# home-connection.net
KiCad netlist of a schematic drawn in EasyEDA Pro
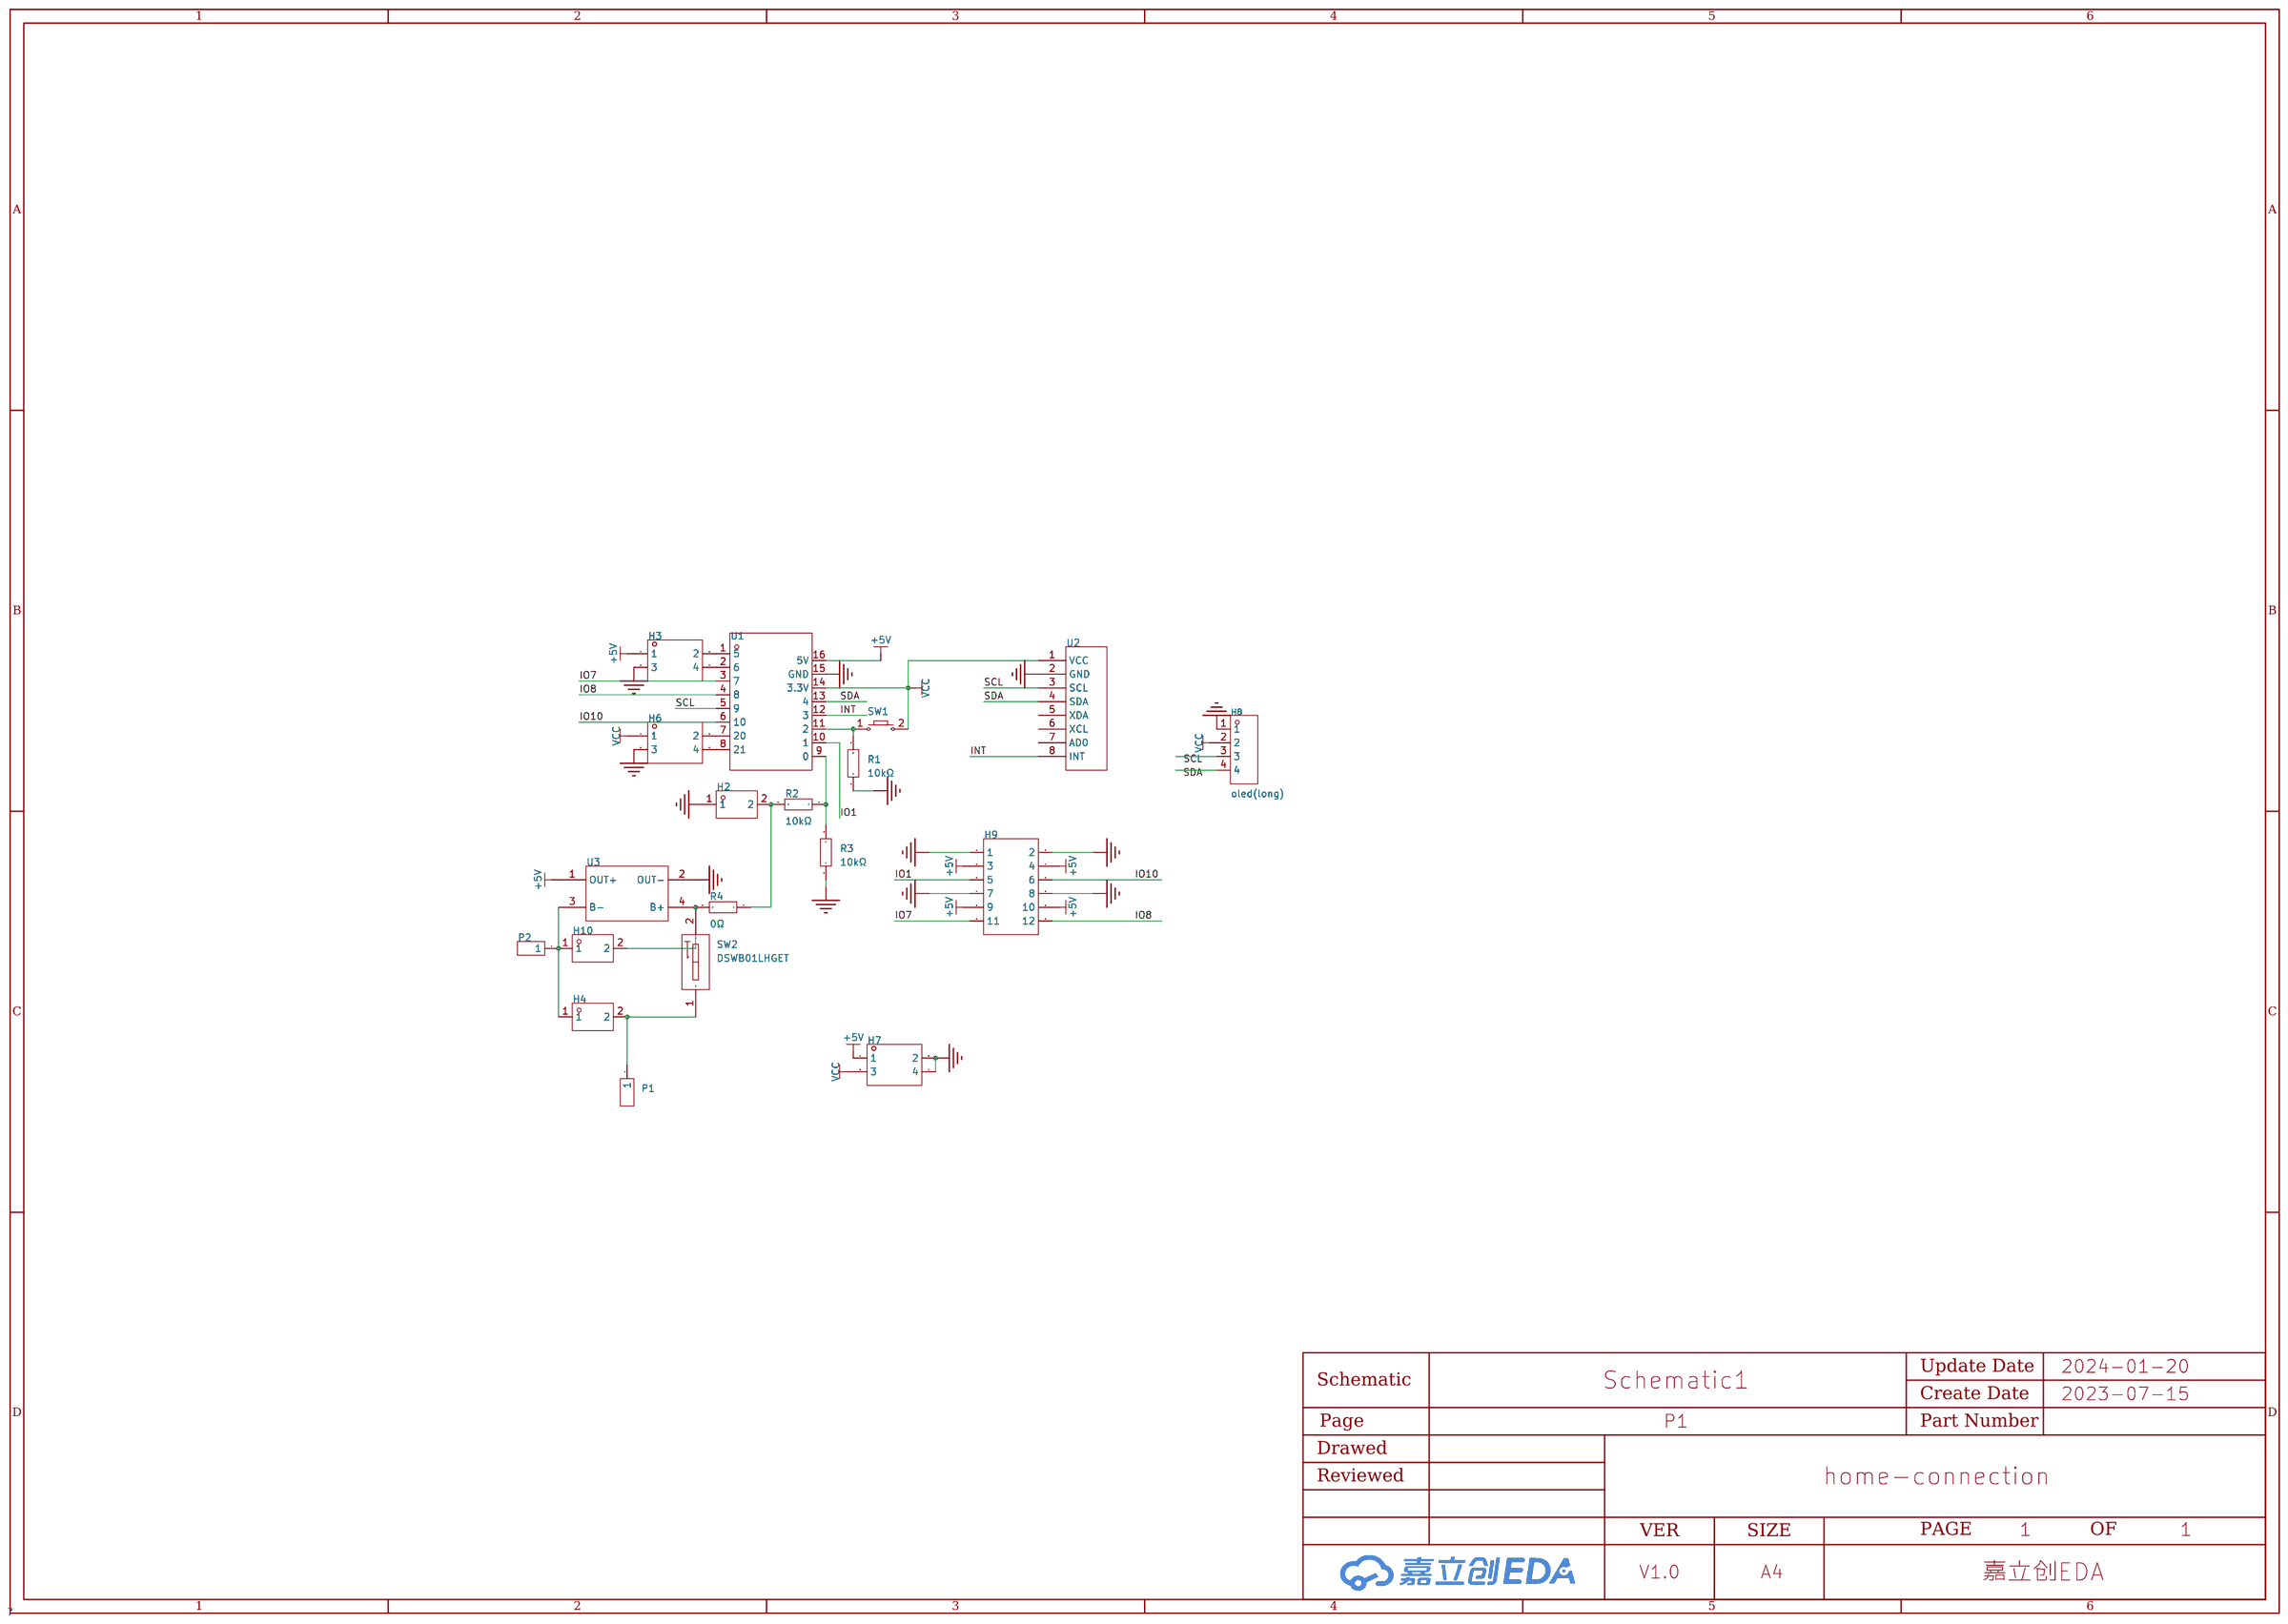
[diagram p0: schematic sheet]

(export (version "E")
  (design (tool "Eeschema 10.0.6"))
  (components
    (comp (ref "H2")
      (value "~")
      (footprint "easyedapro:HDR-TH_2P-P2.54-V-M-2")
      (libsource (lib "easyedapro") (part "HDR-M-2.54_2x1"))
    )
    (comp (ref "H3")
      (value "~")
      (footprint "easyedapro:HDR-TH_4P-P2.54-V-F-R2-C2-S2.54")
      (libsource (lib "easyedapro") (part "HDR-F-2.54_2x2"))
    )
    (comp (ref "H4")
      (value "~")
      (footprint "easyedapro:HDR-TH_2P-P2.54-V-M-2")
      (libsource (lib "easyedapro") (part "HDR-M-2.54_2x1"))
    )
    (comp (ref "H6")
      (value "~")
      (footprint "easyedapro:HDR-TH_4P-P2.54-V-F-R2-C2-S2.54")
      (libsource (lib "easyedapro") (part "HDR-F-2.54_2x2"))
    )
    (comp (ref "H7")
      (value "~")
      (footprint "easyedapro:HDR-TH_4P-P2.54-V-F-R2-C2-S2.54")
      (libsource (lib "easyedapro") (part "HDR-F-2.54_2x2"))
    )
    (comp (ref "H8")
      (value "oled(long)")
      (footprint "easyedapro:HDR-TH_4P-P2.54-V-M")
      (fields (field (name "Manufacturer") "XFCN(兴飞)"))
      (libsource (lib "easyedapro") (part "PZ254V-11-04P_C2691448"))
    )
    (comp (ref "H9")
      (value "~")
      (footprint "easyedapro:HDR-TH_12P-P2.54-V-M-R2-C6-S2.54")
      (libsource (lib "easyedapro") (part "HDR-F-2.54_2x6"))
    )
    (comp (ref "H10")
      (value "~")
      (footprint "easyedapro:HDR-TH_2P-P2.54-V-M-2")
      (libsource (lib "easyedapro") (part "HDR-M-2.54_2x1"))
    )
    (comp (ref "P1")
      (value "~")
      (footprint "easyedapro:HDR-TH_1P-P2.54-V-M")
      (description "间距:-;总PIN位数:1;排数:1;插针结构:-;行距:-;安装类型:直插;圆针/方针:-;额定电流:-;额定电压:-;配合针长度:-;塑高:-;触头材质:-;触头镀层:-;颜色:黑色;")
      (fields (field (name "Manufacturer Part") "2.54-1*1P针") (field (name "Manufacturer") "BOOMELE(博穆精密)"))
      (libsource (lib "easyedapro") (part "Header-Male-2.54_1x1"))
    )
    (comp (ref "P2")
      (value "~")
      (footprint "easyedapro:HDR-TH_1P-P2.54-V-M")
      (description "间距:-;总PIN位数:1;排数:1;插针结构:-;行距:-;安装类型:直插;圆针/方针:-;额定电流:-;额定电压:-;配合针长度:-;塑高:-;触头材质:-;触头镀层:-;颜色:黑色;")
      (fields (field (name "Manufacturer Part") "2.54-1*1P针") (field (name "Manufacturer") "BOOMELE(博穆精密)"))
      (libsource (lib "easyedapro") (part "Header-Male-2.54_1x1"))
    )
    (comp (ref "R1")
      (value "10kΩ")
      (footprint "easyedapro:R0603")
      (description "电阻类型:厚膜电阻;阻值:10kΩ;精度:±1%;功率:100mW;")
      (fields
        (field (name "Manufacturer Part") "0603WAF1002T5E")
        (field (name "Manufacturer") "UNI-ROYAL(厚声)")
      )
      (libsource (lib "easyedapro") (part "0603WAF1002T5E"))
    )
    (comp (ref "R2")
      (value "10kΩ")
      (footprint "easyedapro:R0603")
      (description "电阻类型:厚膜电阻;阻值:10kΩ;精度:±1%;功率:100mW;")
      (fields
        (field (name "Manufacturer Part") "0603WAF1002T5E")
        (field (name "Manufacturer") "UNI-ROYAL(厚声)")
      )
      (libsource (lib "easyedapro") (part "0603WAF1002T5E"))
    )
    (comp (ref "R3")
      (value "10kΩ")
      (footprint "easyedapro:R0603")
      (description "电阻类型:厚膜电阻;阻值:10kΩ;精度:±1%;功率:100mW;")
      (fields
        (field (name "Manufacturer Part") "0603WAF1002T5E")
        (field (name "Manufacturer") "UNI-ROYAL(厚声)")
      )
      (libsource (lib "easyedapro") (part "0603WAF1002T5E"))
    )
    (comp (ref "R4")
      (value "0Ω")
      (footprint "easyedapro:R0603")
      (description "电阻类型:厚膜电阻;阻值:10kΩ;精度:±1%;功率:100mW;")
      (fields
        (field (name "Manufacturer Part") "0603WAF1002T5E")
        (field (name "Manufacturer") "UNI-ROYAL(厚声)")
      )
      (libsource (lib "easyedapro") (part "0603WAF1002T5E"))
    )
    (comp (ref "SW1")
      (value "~")
      (footprint "easyedapro:Key_SMD_3x4x2")
      (libsource (lib "easyedapro") (part "轻触按键x2"))
    )
    (comp (ref "SW2")
      (value "DSWB01LHGET")
      (footprint "easyedapro:SW-TH_DSWB01LHGET")
      (description "类型:平拨,凸起式;电路结构:单刀单掷;开关位数:1;使用寿命:-;颜色:红色;")
      (fields (field (name "Manufacturer") "YE"))
      (libsource (lib "easyedapro") (part "DSWB01LHGET"))
    )
    (comp (ref "U1")
      (value "2.4GHz")
      (footprint "easyedapro:ESP32-C3-SUPERMINI")
      (description "核心处理器:ESP32-C3芯片;频率:2.4GHz;发射功率:20.5dBm;")
      (fields
        (field (name "Manufacturer Part") "ESP32-C3-WROOM-02U-N4")
        (field (name "Manufacturer") "ESPRESSIF(乐鑫)")
      )
      (libsource (lib "easyedapro") (part "ESP32-C3-SUPERMINI"))
    )
    (comp (ref "U2")
      (value "~")
      (footprint "easyedapro:GY-521")
      (description "MPU6050")
      (libsource (lib "easyedapro") (part "GY-521"))
    )
    (comp (ref "U3")
      (value "~")
      (footprint "easyedapro:BAT-CHARGE")
      (description "电池充电模块")
      (libsource (lib "easyedapro") (part "BAT-CHARGE"))
    )
  )
  (nets
    (net (code "1") (name "+5V") (class "Default")
      (node (ref "H3") (pin "1") (pinfunction "1_1") (pintype "input"))
      (node (ref "H7") (pin "1") (pinfunction "1_1") (pintype "input"))
      (node (ref "H9") (pin "10") (pinfunction "10_10") (pintype "input"))
      (node (ref "H9") (pin "3") (pinfunction "3_3") (pintype "input"))
      (node (ref "H9") (pin "4") (pinfunction "4_4") (pintype "input"))
      (node (ref "H9") (pin "9") (pinfunction "9_9") (pintype "input"))
      (node (ref "U1") (pin "16") (pinfunction "5V_16") (pintype "unspecified"))
      (node (ref "U3") (pin "1") (pinfunction "OUT+_1") (pintype "input"))
    )
    (net (code "2") (name "/INT") (class "Default")
      (node (ref "U1") (pin "12") (pinfunction "3_12") (pintype "bidirectional"))
      (node (ref "U2") (pin "8") (pinfunction "INT_8") (pintype "input"))
    )
    (net (code "3") (name "/IO1") (class "Default")
      (node (ref "H9") (pin "5") (pinfunction "5_5") (pintype "input"))
      (node (ref "U1") (pin "10") (pinfunction "1_10") (pintype "bidirectional"))
    )
    (net (code "4") (name "/IO7") (class "Default")
      (node (ref "H9") (pin "11") (pinfunction "11_11") (pintype "input"))
      (node (ref "U1") (pin "3") (pinfunction "7_3") (pintype "unspecified"))
    )
    (net (code "5") (name "/IO8") (class "Default")
      (node (ref "H9") (pin "12") (pinfunction "12_12") (pintype "input"))
      (node (ref "U1") (pin "4") (pinfunction "8_4") (pintype "unspecified"))
    )
    (net (code "6") (name "/IO10") (class "Default")
      (node (ref "H9") (pin "6") (pinfunction "6_6") (pintype "input"))
      (node (ref "U1") (pin "6") (pinfunction "10_6") (pintype "unspecified"))
    )
    (net (code "7") (name "/SCL") (class "Default")
      (node (ref "H8") (pin "3") (pinfunction "3_3") (pintype "input"))
      (node (ref "U1") (pin "5") (pinfunction "9_5") (pintype "unspecified"))
      (node (ref "U2") (pin "3") (pinfunction "SCL_3") (pintype "input"))
    )
    (net (code "8") (name "/SDA") (class "Default")
      (node (ref "H8") (pin "4") (pinfunction "4_4") (pintype "input"))
      (node (ref "U1") (pin "13") (pinfunction "4_13") (pintype "bidirectional"))
      (node (ref "U2") (pin "4") (pinfunction "SDA_4") (pintype "input"))
    )
    (net (code "9") (name "GND") (class "Default")
      (node (ref "H2") (pin "1") (pinfunction "1_1") (pintype "input"))
      (node (ref "H3") (pin "3") (pinfunction "3_3") (pintype "input"))
      (node (ref "H6") (pin "3") (pinfunction "3_3") (pintype "input"))
      (node (ref "H7") (pin "2") (pinfunction "2_2") (pintype "input"))
      (node (ref "H7") (pin "4") (pinfunction "4_4") (pintype "input"))
      (node (ref "H8") (pin "1") (pinfunction "1_1") (pintype "input"))
      (node (ref "H9") (pin "1") (pinfunction "1_1") (pintype "input"))
      (node (ref "H9") (pin "2") (pinfunction "2_2") (pintype "input"))
      (node (ref "H9") (pin "7") (pinfunction "7_7") (pintype "input"))
      (node (ref "H9") (pin "8") (pinfunction "8_8") (pintype "input"))
      (node (ref "R1") (pin "1") (pinfunction "1_1") (pintype "input"))
      (node (ref "R3") (pin "1") (pinfunction "1_1") (pintype "input"))
      (node (ref "U1") (pin "15") (pinfunction "GND_15") (pintype "unspecified"))
      (node (ref "U2") (pin "2") (pinfunction "GND_2") (pintype "input"))
      (node (ref "U3") (pin "2") (pinfunction "OUT-_2") (pintype "input"))
    )
    (net (code "10") (name "Net-(H2-Pad2)") (class "Default")
      (node (ref "H2") (pin "2") (pinfunction "2_2") (pintype "input"))
      (node (ref "R2") (pin "2") (pinfunction "2_2") (pintype "input"))
      (node (ref "R4") (pin "1") (pinfunction "1_1") (pintype "input"))
    )
    (net (code "11") (name "Net-(SW2-A1)") (class "Default")
      (node (ref "H4") (pin "2") (pinfunction "2_2") (pintype "input"))
      (node (ref "P1") (pin "1") (pinfunction "1_1") (pintype "input"))
      (node (ref "SW2") (pin "1") (pinfunction "A1_1") (pintype "input"))
    )
    (net (code "12") (name "Net-(U1-0)") (class "Default")
      (node (ref "R2") (pin "1") (pinfunction "1_1") (pintype "input"))
      (node (ref "R3") (pin "2") (pinfunction "2_2") (pintype "input"))
      (node (ref "U1") (pin "9") (pinfunction "0_9") (pintype "unspecified"))
    )
    (net (code "13") (name "Net-(U1-2)") (class "Default")
      (node (ref "R1") (pin "2") (pinfunction "2_2") (pintype "input"))
      (node (ref "SW1") (pin "1") (pinfunction "1_1") (pintype "input"))
      (node (ref "U1") (pin "11") (pinfunction "2_11") (pintype "unspecified"))
    )
    (net (code "14") (name "Net-(U1-5)") (class "Default")
      (node (ref "H3") (pin "2") (pinfunction "2_2") (pintype "input"))
      (node (ref "U1") (pin "1") (pinfunction "5_1") (pintype "unspecified"))
    )
    (net (code "15") (name "Net-(U1-6)") (class "Default")
      (node (ref "H3") (pin "4") (pinfunction "4_4") (pintype "input"))
      (node (ref "U1") (pin "2") (pinfunction "6_2") (pintype "unspecified"))
    )
    (net (code "16") (name "Net-(U1-20)") (class "Default")
      (node (ref "H6") (pin "2") (pinfunction "2_2") (pintype "input"))
      (node (ref "U1") (pin "7") (pinfunction "20_7") (pintype "unspecified"))
    )
    (net (code "17") (name "Net-(U1-21)") (class "Default")
      (node (ref "H6") (pin "4") (pinfunction "4_4") (pintype "input"))
      (node (ref "U1") (pin "8") (pinfunction "21_8") (pintype "unspecified"))
    )
    (net (code "18") (name "Net-(U3-B+)") (class "Default")
      (node (ref "H10") (pin "2") (pinfunction "2_2") (pintype "input"))
      (node (ref "R4") (pin "2") (pinfunction "2_2") (pintype "input"))
      (node (ref "SW2") (pin "2") (pinfunction "2_2") (pintype "input"))
      (node (ref "U3") (pin "4") (pinfunction "B+_4") (pintype "input"))
    )
    (net (code "19") (name "Net-(U3-B-)") (class "Default")
      (node (ref "H10") (pin "1") (pinfunction "1_1") (pintype "input"))
      (node (ref "H4") (pin "1") (pinfunction "1_1") (pintype "input"))
      (node (ref "P2") (pin "1") (pinfunction "1_1") (pintype "input"))
      (node (ref "U3") (pin "3") (pinfunction "B-_3") (pintype "input"))
    )
    (net (code "20") (name "VCC") (class "Default")
      (node (ref "H6") (pin "1") (pinfunction "1_1") (pintype "input"))
      (node (ref "H7") (pin "3") (pinfunction "3_3") (pintype "input"))
      (node (ref "H8") (pin "2") (pinfunction "2_2") (pintype "input"))
      (node (ref "SW1") (pin "2") (pinfunction "2_2") (pintype "input"))
      (node (ref "U1") (pin "14") (pinfunction "3.3V_14") (pintype "bidirectional"))
      (node (ref "U2") (pin "1") (pinfunction "VCC_1") (pintype "input"))
    )
    (net (code "21") (name "unconnected-(U2-AD0-Pad7)") (class "Default")
      (node (ref "U2") (pin "7") (pinfunction "AD0_7") (pintype "input"))
    )
    (net (code "22") (name "unconnected-(U2-XCL-Pad6)") (class "Default")
      (node (ref "U2") (pin "6") (pinfunction "XCL_6") (pintype "input"))
    )
    (net (code "23") (name "unconnected-(U2-XDA-Pad5)") (class "Default")
      (node (ref "U2") (pin "5") (pinfunction "XDA_5") (pintype "input"))
    )
  )
)
